# OMODRI_QuadEnc.net
KiCad netlist of a schematic drawn in Altium Designer
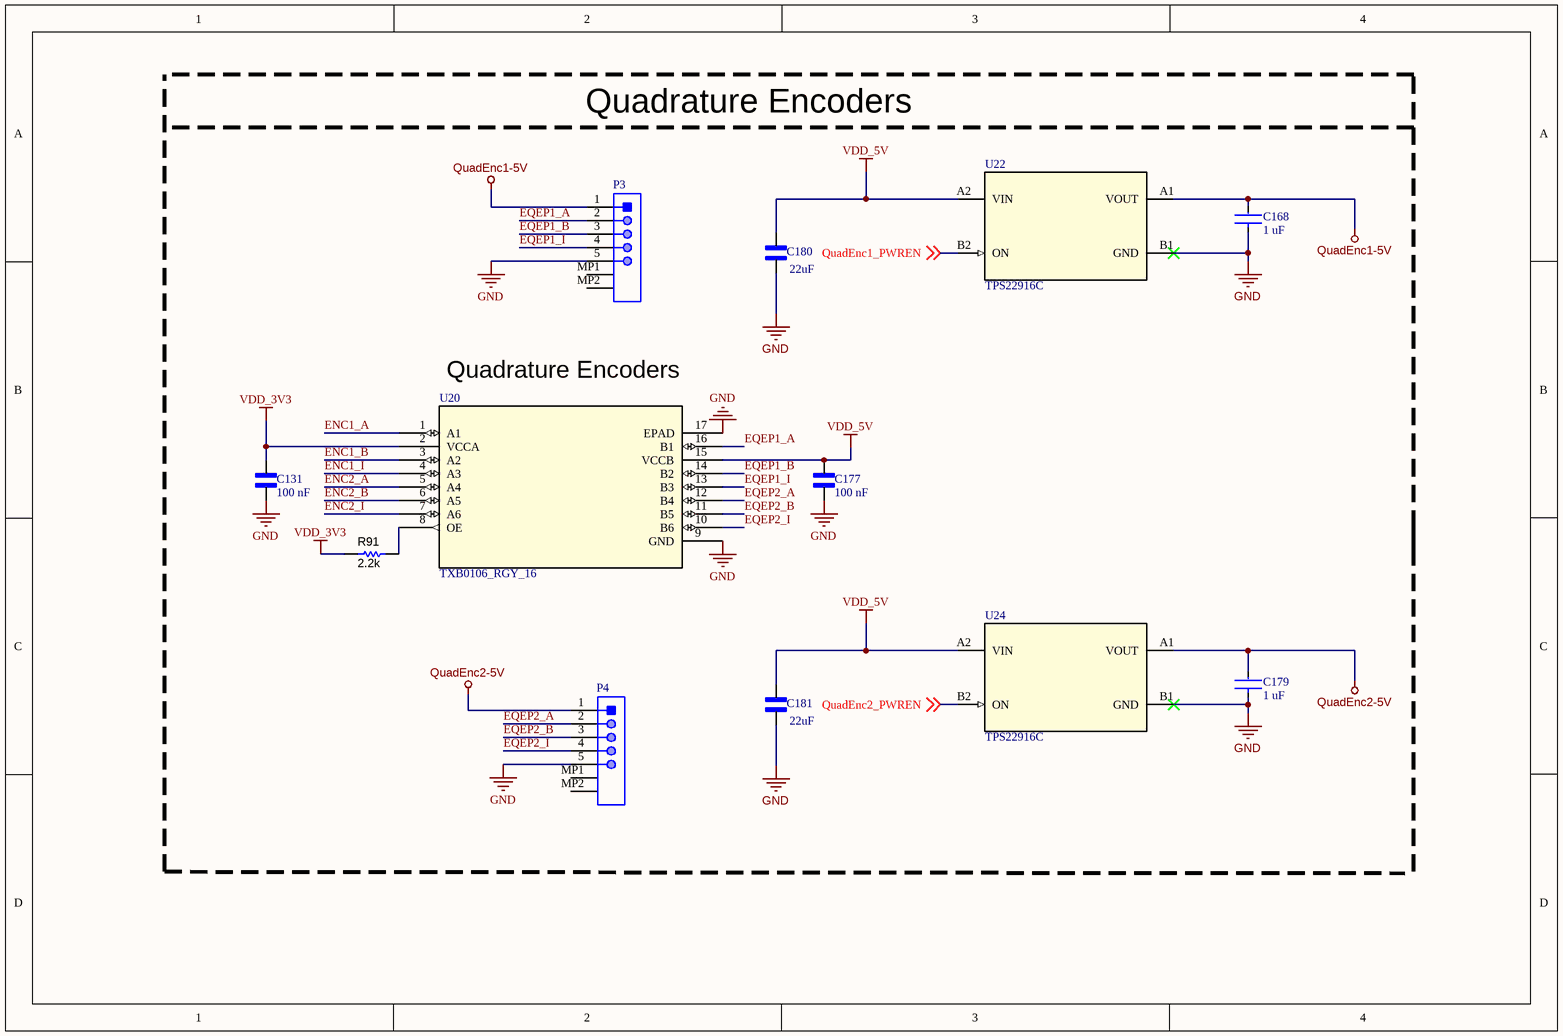
[diagram p0: OMODRI_QuadEnc.SchDoc]

(export (version "E")
  (design (tool "Eeschema 10.0.6"))
  (components
    (comp (ref "C131")
      (value "100 nF")
      (footprint "CAPC0603X33N")
      (description "SMD Capacitor X5R_EIA_ with Capacitance: 0.10uF Tol. 10%. Rated Voltage: 25Vdc")
      (fields (field (name "MF") "Murata") (field (name "MP") "GRM033R61E104KE14D"))
      (libsource (lib "GRM033R61E104KE14D") (part "GRM033R61E104KE14D"))
    )
    (comp (ref "C168")
      (value "1 uF")
      (footprint "FP-CC0201-BA-MFG")
      (description "CAP CER 1UF 6.3V X5R 0201")
      (fields (field (name "TOLERANCE") "0.2") (field (name "MANUFACTURER") "Yageo"))
      (libsource (lib "Altium Content Vault") (part "11868f565c42a9108669ba33697ecf6"))
    )
    (comp (ref "C177")
      (value "100 nF")
      (footprint "CAPC0603X33N")
      (description "SMD Capacitor X5R_EIA_ with Capacitance: 0.10uF Tol. 10%. Rated Voltage: 25Vdc")
      (fields (field (name "MF") "Murata") (field (name "MP") "GRM033R61E104KE14D"))
      (libsource (lib "GRM033R61E104KE14D") (part "GRM033R61E104KE14D"))
    )
    (comp (ref "C179")
      (value "1 uF")
      (footprint "FP-CC0201-BA-MFG")
      (description "CAP CER 1UF 6.3V X5R 0201")
      (fields (field (name "TOLERANCE") "0.2") (field (name "MANUFACTURER") "Yageo"))
      (libsource (lib "Altium Content Vault") (part "11868f565c42a9108669ba33697ecf6"))
    )
    (comp (ref "C180")
      (value "22uF")
      (footprint "CAPC1005X55N")
      (description "22µF ±20% 6.3V Ceramic Capacitor X5R 0402 (1005 Metric)")
      (fields (field (name "MP") "CL05A226MQ5N6J8") (field (name "MF") "Samsung Electro-Mechanics"))
      (libsource (lib "CL05A226MQ5N6J8") (part "CL05A226MQ5N6J8"))
    )
    (comp (ref "C181")
      (value "22uF")
      (footprint "CAPC1005X55N")
      (description "22µF ±20% 6.3V Ceramic Capacitor X5R 0402 (1005 Metric)")
      (fields (field (name "MP") "CL05A226MQ5N6J8") (field (name "MF") "Samsung Electro-Mechanics"))
      (libsource (lib "CL05A226MQ5N6J8") (part "CL05A226MQ5N6J8"))
    )
    (comp (ref "P3")
      (value "BM05B-GHS-TBT(LF)(SN)")
      (footprint "JST-BM05B-GHS-TBT_V")
      (fields (field (name "MANUFACTURER") "JST"))
      (libsource (lib "JST_GH") (part "CMP-2000-05958-1"))
    )
    (comp (ref "P4")
      (value "BM05B-GHS-TBT(LF)(SN)")
      (footprint "JST-BM05B-GHS-TBT_V")
      (fields (field (name "MANUFACTURER") "JST"))
      (libsource (lib "JST_GH") (part "CMP-2000-05958-1"))
    )
    (comp (ref "R91")
      (value "CRCW04022K20JNED")
      (footprint "0402")
      (description "RES, 2.2 k, 5%, 0.063 W, AEC-Q200 Grade 0, 0402")
      (fields (field (name "MANUFACTURER") "Vishay-Dale") (field (name "VALUEDISPLAYED") "2.2k"))
      (libsource (lib "Altium Vault - TI") (part "Resistor"))
    )
    (comp (ref "U20")
      (value "TXB0106_RGY_16")
      (footprint "RGY16_2P55X2P05")
      (fields
        (field (name "MANUFACTURER_PART_NUMBER") "txb0106_rgy_16")
        (field (name "GENERIC_PART_NUMBER") "TXB0106")
        (field (name "MANUFACTURER") "Texas Instruments")
      )
      (libsource (lib "Texas_Instruments") (part "TXB0106_RGY_16"))
    )
    (comp (ref "U22")
      (value "TPS22916C")
      (footprint "YFP0004ABAB")
      (description "TPS22916CY Single-Channel Ultra-Low Leakage Load Switch 2A 60 mO 1V to 5.5V 4-Pin DSBGA T/R")
      (fields
        (field (name "MANUFACTURER") "Texas Instruments")
        (field (name "MANUFACTURER PART NUMBER") "TPS22916CYFPR")
      )
      (libsource (lib "Texas_Instruments") (part "TPS22916C"))
    )
    (comp (ref "U24")
      (value "TPS22916C")
      (footprint "YFP0004ABAB")
      (description "TPS22916CY Single-Channel Ultra-Low Leakage Load Switch 2A 60 mO 1V to 5.5V 4-Pin DSBGA T/R")
      (fields
        (field (name "MANUFACTURER") "Texas Instruments")
        (field (name "MANUFACTURER PART NUMBER") "TPS22916CYFPR")
      )
      (libsource (lib "Texas_Instruments") (part "TPS22916C"))
    )
  )
  (nets
    (net (code "1") (name "/ENC1_A") (class "Default")
      (node (ref "U20") (pin "1") (pinfunction "A1_1") (pintype "bidirectional"))
    )
    (net (code "2") (name "/ENC1_B") (class "Default")
      (node (ref "U20") (pin "3") (pinfunction "A2_3") (pintype "bidirectional"))
    )
    (net (code "3") (name "/ENC1_I") (class "Default")
      (node (ref "U20") (pin "4") (pinfunction "A3_4") (pintype "bidirectional"))
    )
    (net (code "4") (name "/ENC2_A") (class "Default")
      (node (ref "U20") (pin "5") (pinfunction "A4_5") (pintype "bidirectional"))
    )
    (net (code "5") (name "/ENC2_B") (class "Default")
      (node (ref "U20") (pin "6") (pinfunction "A5_6") (pintype "bidirectional"))
    )
    (net (code "6") (name "/ENC2_I") (class "Default")
      (node (ref "U20") (pin "7") (pinfunction "A6_7") (pintype "bidirectional"))
    )
    (net (code "7") (name "/EQEP1_A") (class "Default")
      (node (ref "P3") (pin "2") (pinfunction "2_2") (pintype "passive"))
      (node (ref "U20") (pin "16") (pinfunction "B1_16") (pintype "bidirectional"))
    )
    (net (code "8") (name "/EQEP1_B") (class "Default")
      (node (ref "P3") (pin "3") (pinfunction "3_3") (pintype "passive"))
      (node (ref "U20") (pin "14") (pinfunction "B2_14") (pintype "bidirectional"))
    )
    (net (code "9") (name "/EQEP1_I") (class "Default")
      (node (ref "P3") (pin "4") (pinfunction "4_4") (pintype "passive"))
      (node (ref "U20") (pin "13") (pinfunction "B3_13") (pintype "bidirectional"))
    )
    (net (code "10") (name "/EQEP2_A") (class "Default")
      (node (ref "P4") (pin "2") (pinfunction "2_2") (pintype "passive"))
      (node (ref "U20") (pin "12") (pinfunction "B4_12") (pintype "bidirectional"))
    )
    (net (code "11") (name "/EQEP2_B") (class "Default")
      (node (ref "P4") (pin "3") (pinfunction "3_3") (pintype "passive"))
      (node (ref "U20") (pin "11") (pinfunction "B5_11") (pintype "bidirectional"))
    )
    (net (code "12") (name "/EQEP2_I") (class "Default")
      (node (ref "P4") (pin "4") (pinfunction "4_4") (pintype "passive"))
      (node (ref "U20") (pin "10") (pinfunction "B6_10") (pintype "bidirectional"))
    )
    (net (code "13") (name "GND") (class "Default")
      (node (ref "C131") (pin "1") (pinfunction "1_1") (pintype "passive"))
      (node (ref "C168") (pin "1") (pinfunction "1_1") (pintype "passive"))
      (node (ref "C177") (pin "1") (pinfunction "1_1") (pintype "passive"))
      (node (ref "C179") (pin "1") (pinfunction "1_1") (pintype "passive"))
      (node (ref "C180") (pin "1") (pinfunction "1_1") (pintype "passive"))
      (node (ref "C181") (pin "1") (pinfunction "1_1") (pintype "passive"))
      (node (ref "P3") (pin "5") (pinfunction "5_5") (pintype "passive"))
      (node (ref "P4") (pin "5") (pinfunction "5_5") (pintype "passive"))
      (node (ref "U20") (pin "17") (pinfunction "EPAD_17") (pintype "passive"))
      (node (ref "U20") (pin "9") (pinfunction "GND_9") (pintype "power_in"))
      (node (ref "U22") (pin "B1") (pinfunction "GND_B1") (pintype "power_in"))
      (node (ref "U24") (pin "B1") (pinfunction "GND_B1") (pintype "power_in"))
    )
    (net (code "14") (name "Net-(U20-OE)") (class "Default")
      (node (ref "R91") (pin "1") (pinfunction "1_1") (pintype "passive"))
      (node (ref "U20") (pin "8") (pinfunction "OE_8") (pintype "output"))
    )
    (net (code "15") (name "QuadEnc1-5V") (class "Default")
      (node (ref "C168") (pin "2") (pinfunction "2_2") (pintype "passive"))
      (node (ref "P3") (pin "1") (pinfunction "1_1") (pintype "passive"))
      (node (ref "U22") (pin "A1") (pinfunction "VOUT_A1") (pintype "power_in"))
    )
    (net (code "16") (name "QuadEnc1_PWREN") (class "Default")
      (node (ref "U22") (pin "B2") (pinfunction "ON_B2") (pintype "input"))
    )
    (net (code "17") (name "QuadEnc2-5V") (class "Default")
      (node (ref "C179") (pin "2") (pinfunction "2_2") (pintype "passive"))
      (node (ref "P4") (pin "1") (pinfunction "1_1") (pintype "passive"))
      (node (ref "U24") (pin "A1") (pinfunction "VOUT_A1") (pintype "power_in"))
    )
    (net (code "18") (name "QuadEnc2_PWREN") (class "Default")
      (node (ref "U24") (pin "B2") (pinfunction "ON_B2") (pintype "input"))
    )
    (net (code "19") (name "VDD_3V3") (class "Default")
      (node (ref "C131") (pin "2") (pinfunction "2_2") (pintype "passive"))
      (node (ref "R91") (pin "2") (pinfunction "2_2") (pintype "passive"))
      (node (ref "U20") (pin "2") (pinfunction "VCCA_2") (pintype "power_in"))
    )
    (net (code "20") (name "VDD_5V") (class "Default")
      (node (ref "C177") (pin "2") (pinfunction "2_2") (pintype "passive"))
      (node (ref "C180") (pin "2") (pinfunction "2_2") (pintype "passive"))
      (node (ref "C181") (pin "2") (pinfunction "2_2") (pintype "passive"))
      (node (ref "U20") (pin "15") (pinfunction "VCCB_15") (pintype "power_in"))
      (node (ref "U22") (pin "A2") (pinfunction "VIN_A2") (pintype "power_in"))
      (node (ref "U24") (pin "A2") (pinfunction "VIN_A2") (pintype "power_in"))
    )
    (net (code "21") (name "unconnected-(P3-PadMP1)") (class "Default")
      (node (ref "P3") (pin "MP1") (pinfunction "MP1_MP1") (pintype "passive"))
    )
    (net (code "22") (name "unconnected-(P3-PadMP2)") (class "Default")
      (node (ref "P3") (pin "MP2") (pinfunction "MP2_MP2") (pintype "passive"))
    )
    (net (code "23") (name "unconnected-(P4-PadMP1)") (class "Default")
      (node (ref "P4") (pin "MP1") (pinfunction "MP1_MP1") (pintype "passive"))
    )
    (net (code "24") (name "unconnected-(P4-PadMP2)") (class "Default")
      (node (ref "P4") (pin "MP2") (pinfunction "MP2_MP2") (pintype "passive"))
    )
  )
)
